# SCH_ESP-CellCore_USB_Interlock_RevA2_CLE.net
KiCad netlist of a schematic drawn in EasyEDA
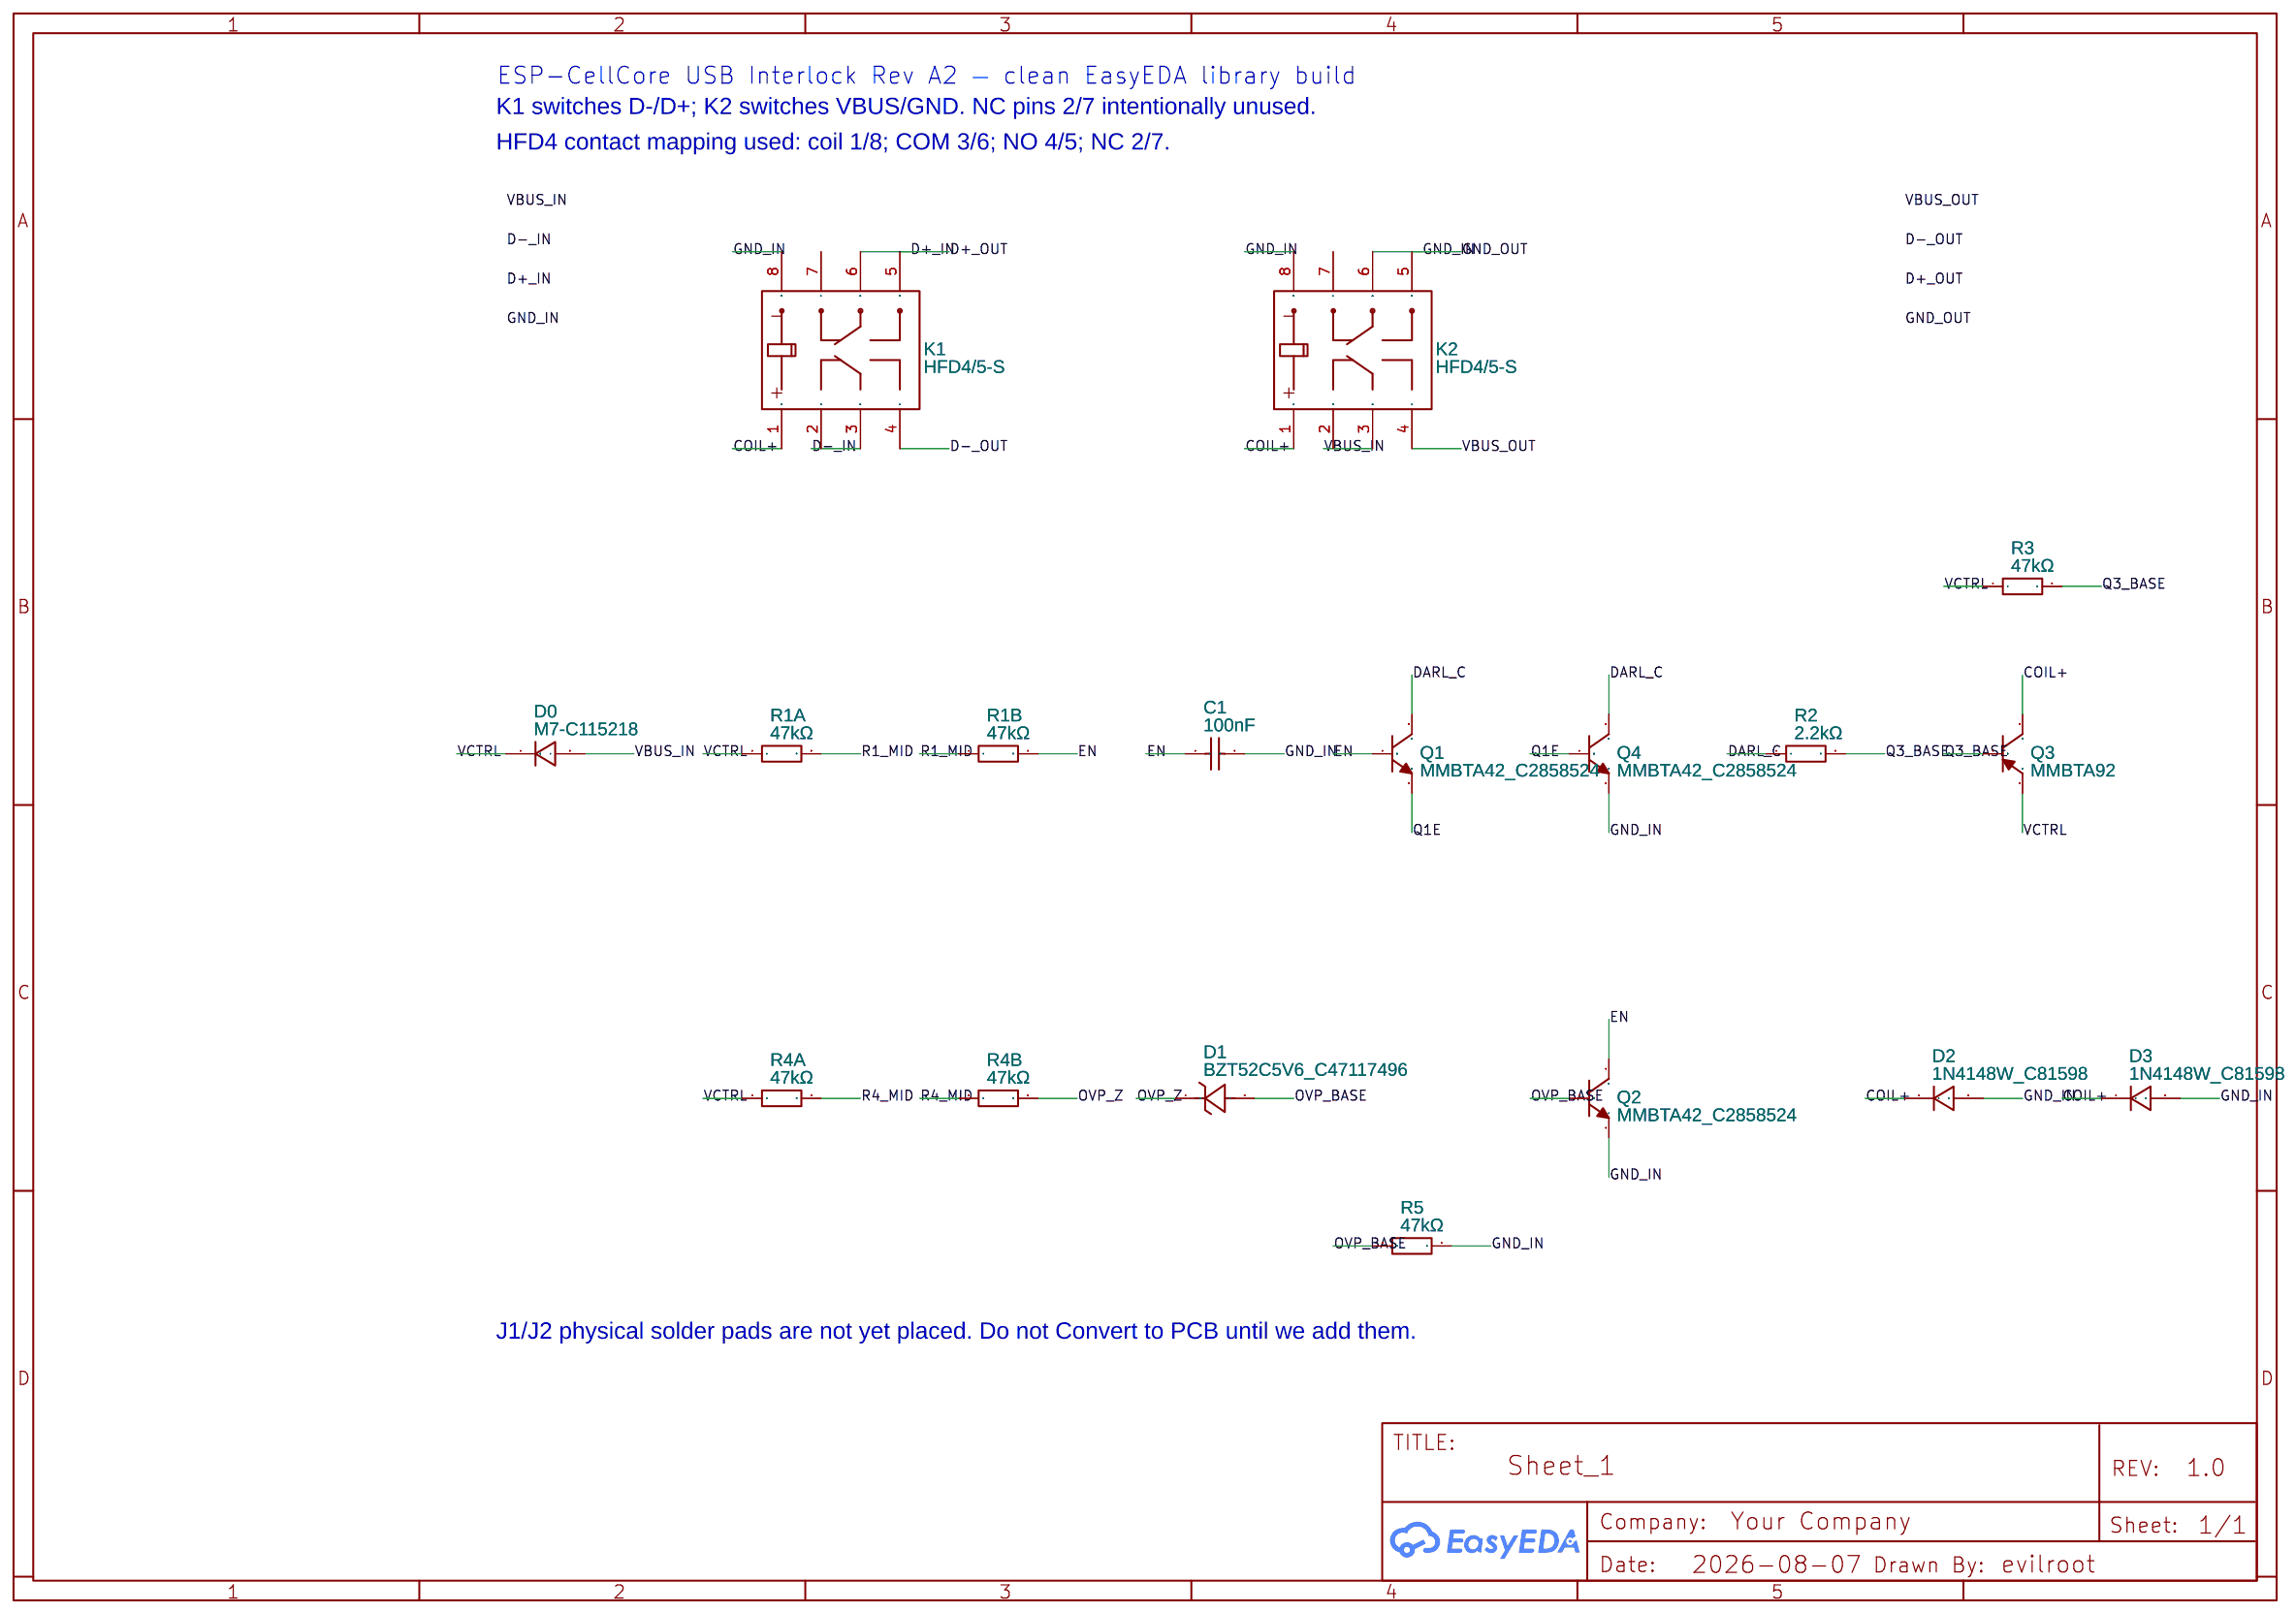
[diagram p0: schematic sheet]

(export (version "E")
  (design (tool "Eeschema 10.0.6"))
  (components
    (comp (ref "C1")
      (value "100nF")
      (fields
        (field (name "Manufacturer Part") "C0805C104K5RAC7800")
        (field (name "Manufacturer") "KEMET(基美)")
      )
      (libsource (lib "") (part "C0805C104K5RACTU"))
    )
    (comp (ref "D0")
      (value "M7-C115218")
      (fields (field (name "Manufacturer Part") "M7") (field (name "Manufacturer") "晶导微电子"))
      (libsource (lib "") (part "M7-C115218"))
    )
    (comp (ref "D1")
      (value "BZT52C5V6_C47117496")
      (fields (field (name "Manufacturer Part") "BZT52C5V6") (field (name "Manufacturer") "baocheng(宝乘)"))
      (libsource (lib "") (part "BZT52C5V6_C47117496"))
    )
    (comp (ref "D2")
      (value "1N4148W_C81598")
      (fields (field (name "Manufacturer Part") "1N4148W") (field (name "Manufacturer") "ST(先科)"))
      (libsource (lib "") (part "1N4148W_C81598"))
    )
    (comp (ref "D3")
      (value "1N4148W_C81598")
      (fields (field (name "Manufacturer Part") "1N4148W") (field (name "Manufacturer") "ST(先科)"))
      (libsource (lib "") (part "1N4148W_C81598"))
    )
    (comp (ref "K1")
      (value "HFD4/5-S")
      (fields (field (name "Manufacturer Part") "HFD4/5-SR") (field (name "Manufacturer") "HF(宏发)"))
      (libsource (lib "") (part "HFD4/5-S"))
    )
    (comp (ref "K2")
      (value "HFD4/5-S")
      (fields (field (name "Manufacturer Part") "HFD4/5-SR") (field (name "Manufacturer") "HF(宏发)"))
      (libsource (lib "") (part "HFD4/5-S"))
    )
    (comp (ref "Q1")
      (value "MMBTA42_C2858524")
      (fields (field (name "Manufacturer Part") "MMBTA42") (field (name "Manufacturer") "MDD(辰达半导体)"))
      (libsource (lib "") (part "MMBTA42_C2858524"))
    )
    (comp (ref "Q2")
      (value "MMBTA42_C2858524")
      (fields (field (name "Manufacturer Part") "MMBTA42") (field (name "Manufacturer") "MDD(辰达半导体)"))
      (libsource (lib "") (part "MMBTA42_C2858524"))
    )
    (comp (ref "Q3")
      (value "MMBTA92")
      (fields (field (name "Manufacturer") "GOODWORK(固得沃克)"))
      (libsource (lib "") (part "MMBTA92"))
    )
    (comp (ref "Q4")
      (value "MMBTA42_C2858524")
      (fields (field (name "Manufacturer Part") "MMBTA42") (field (name "Manufacturer") "MDD(辰达半导体)"))
      (libsource (lib "") (part "MMBTA42_C2858524"))
    )
    (comp (ref "R1A")
      (value "47kΩ")
      (fields (field (name "Manufacturer Part") "AC0805FR-0747KL") (field (name "Manufacturer") "YAGEO(国巨)"))
      (libsource (lib "") (part "AC0805FR-0747KL_4"))
    )
    (comp (ref "R1B")
      (value "47kΩ")
      (fields (field (name "Manufacturer Part") "AC0805FR-0747KL") (field (name "Manufacturer") "YAGEO(国巨)"))
      (libsource (lib "") (part "AC0805FR-0747KL"))
    )
    (comp (ref "R2")
      (value "2.2kΩ")
      (fields
        (field (name "Manufacturer Part") "0805W8F2201T5E")
        (field (name "Manufacturer") "UNI-ROYAL(厚声)")
      )
      (libsource (lib "") (part "0805W8F2201T5E"))
    )
    (comp (ref "R3")
      (value "47kΩ")
      (fields (field (name "Manufacturer Part") "AC0805FR-0747KL") (field (name "Manufacturer") "YAGEO(国巨)"))
      (libsource (lib "") (part "AC0805FR-0747KL_3"))
    )
    (comp (ref "R4A")
      (value "47kΩ")
      (fields (field (name "Manufacturer Part") "AC0805FR-0747KL") (field (name "Manufacturer") "YAGEO(国巨)"))
      (libsource (lib "") (part "AC0805FR-0747KL_2"))
    )
    (comp (ref "R4B")
      (value "47kΩ")
      (fields (field (name "Manufacturer Part") "AC0805FR-0747KL") (field (name "Manufacturer") "YAGEO(国巨)"))
      (libsource (lib "") (part "AC0805FR-0747KL_1"))
    )
    (comp (ref "R5")
      (value "47kΩ")
      (fields (field (name "Manufacturer Part") "AC0805FR-0747KL") (field (name "Manufacturer") "YAGEO(国巨)"))
      (libsource (lib "") (part "AC0805FR-0747KL_3"))
    )
  )
  (nets
    (net (code "1") (name "/COIL+") (class "Default")
      (node (ref "D2") (pin "1") (pinfunction "K_1") (pintype "unspecified"))
      (node (ref "D3") (pin "1") (pinfunction "K_1") (pintype "unspecified"))
      (node (ref "K1") (pin "1") (pinfunction "1_1") (pintype "input"))
      (node (ref "K2") (pin "1") (pinfunction "1_1") (pintype "input"))
      (node (ref "Q3") (pin "3") (pinfunction "C_3") (pintype "input"))
    )
    (net (code "2") (name "/D+_IN") (class "Default")
      (node (ref "K1") (pin "5") (pinfunction "5_5") (pintype "input"))
      (node (ref "K1") (pin "6") (pinfunction "6_6") (pintype "input"))
    )
    (net (code "3") (name "/D-_IN") (class "Default")
      (node (ref "K1") (pin "3") (pinfunction "3_3") (pintype "input"))
    )
    (net (code "4") (name "/D-_OUT") (class "Default")
      (node (ref "K1") (pin "4") (pinfunction "4_4") (pintype "input"))
    )
    (net (code "5") (name "/DARL_C") (class "Default")
      (node (ref "Q1") (pin "3") (pinfunction "C_3") (pintype "input"))
      (node (ref "Q4") (pin "3") (pinfunction "C_3") (pintype "input"))
      (node (ref "R2") (pin "1") (pinfunction "1_1") (pintype "input"))
    )
    (net (code "6") (name "/EN") (class "Default")
      (node (ref "C1") (pin "1") (pinfunction "1_1") (pintype "input"))
      (node (ref "Q1") (pin "1") (pinfunction "B_1") (pintype "input"))
      (node (ref "Q2") (pin "3") (pinfunction "C_3") (pintype "input"))
      (node (ref "R1B") (pin "2") (pinfunction "2_2") (pintype "unspecified"))
    )
    (net (code "7") (name "/GND_IN") (class "Default")
      (node (ref "C1") (pin "2") (pinfunction "2_2") (pintype "input"))
      (node (ref "D2") (pin "2") (pinfunction "A_2") (pintype "unspecified"))
      (node (ref "D3") (pin "2") (pinfunction "A_2") (pintype "unspecified"))
      (node (ref "K1") (pin "8") (pinfunction "8_8") (pintype "input"))
      (node (ref "K2") (pin "5") (pinfunction "5_5") (pintype "input"))
      (node (ref "K2") (pin "6") (pinfunction "6_6") (pintype "input"))
      (node (ref "K2") (pin "8") (pinfunction "8_8") (pintype "input"))
      (node (ref "Q2") (pin "2") (pinfunction "E_2") (pintype "input"))
      (node (ref "Q4") (pin "2") (pinfunction "E_2") (pintype "input"))
      (node (ref "R5") (pin "2") (pinfunction "2_2") (pintype "unspecified"))
    )
    (net (code "8") (name "/OVP_BASE") (class "Default")
      (node (ref "D1") (pin "2") (pinfunction "A_2") (pintype "unspecified"))
      (node (ref "Q2") (pin "1") (pinfunction "B_1") (pintype "input"))
      (node (ref "R5") (pin "1") (pinfunction "1_1") (pintype "unspecified"))
    )
    (net (code "9") (name "/OVP_Z") (class "Default")
      (node (ref "D1") (pin "1") (pinfunction "C_1") (pintype "unspecified"))
      (node (ref "R4B") (pin "2") (pinfunction "2_2") (pintype "unspecified"))
    )
    (net (code "10") (name "/Q1E") (class "Default")
      (node (ref "Q1") (pin "2") (pinfunction "E_2") (pintype "input"))
      (node (ref "Q4") (pin "1") (pinfunction "B_1") (pintype "input"))
    )
    (net (code "11") (name "/Q3_BASE") (class "Default")
      (node (ref "Q3") (pin "1") (pinfunction "B_1") (pintype "input"))
      (node (ref "R2") (pin "2") (pinfunction "2_2") (pintype "input"))
      (node (ref "R3") (pin "2") (pinfunction "2_2") (pintype "unspecified"))
    )
    (net (code "12") (name "/R1_MID") (class "Default")
      (node (ref "R1A") (pin "2") (pinfunction "2_2") (pintype "unspecified"))
      (node (ref "R1B") (pin "1") (pinfunction "1_1") (pintype "unspecified"))
    )
    (net (code "13") (name "/R4_MID") (class "Default")
      (node (ref "R4A") (pin "2") (pinfunction "2_2") (pintype "unspecified"))
      (node (ref "R4B") (pin "1") (pinfunction "1_1") (pintype "unspecified"))
    )
    (net (code "14") (name "/VBUS_IN") (class "Default")
      (node (ref "D0") (pin "2") (pinfunction "A_2") (pintype "unspecified"))
      (node (ref "K2") (pin "3") (pinfunction "3_3") (pintype "input"))
    )
    (net (code "15") (name "/VBUS_OUT") (class "Default")
      (node (ref "K2") (pin "4") (pinfunction "4_4") (pintype "input"))
    )
    (net (code "16") (name "/VCTRL") (class "Default")
      (node (ref "D0") (pin "1") (pinfunction "C_1") (pintype "unspecified"))
      (node (ref "Q3") (pin "2") (pinfunction "E_2") (pintype "input"))
      (node (ref "R1A") (pin "1") (pinfunction "1_1") (pintype "unspecified"))
      (node (ref "R3") (pin "1") (pinfunction "1_1") (pintype "unspecified"))
      (node (ref "R4A") (pin "1") (pinfunction "1_1") (pintype "unspecified"))
    )
    (net (code "17") (name "unconnected-(K1-Pad2)") (class "Default")
      (node (ref "K1") (pin "2") (pinfunction "2_2") (pintype "input"))
    )
    (net (code "18") (name "unconnected-(K1-Pad7)") (class "Default")
      (node (ref "K1") (pin "7") (pinfunction "7_7") (pintype "input"))
    )
    (net (code "19") (name "unconnected-(K2-Pad2)") (class "Default")
      (node (ref "K2") (pin "2") (pinfunction "2_2") (pintype "input"))
    )
    (net (code "20") (name "unconnected-(K2-Pad7)") (class "Default")
      (node (ref "K2") (pin "7") (pinfunction "7_7") (pintype "input"))
    )
  )
)
